# Tiefenentladeschutz-addon.net
KiCad netlist of a schematic drawn in EAGLE
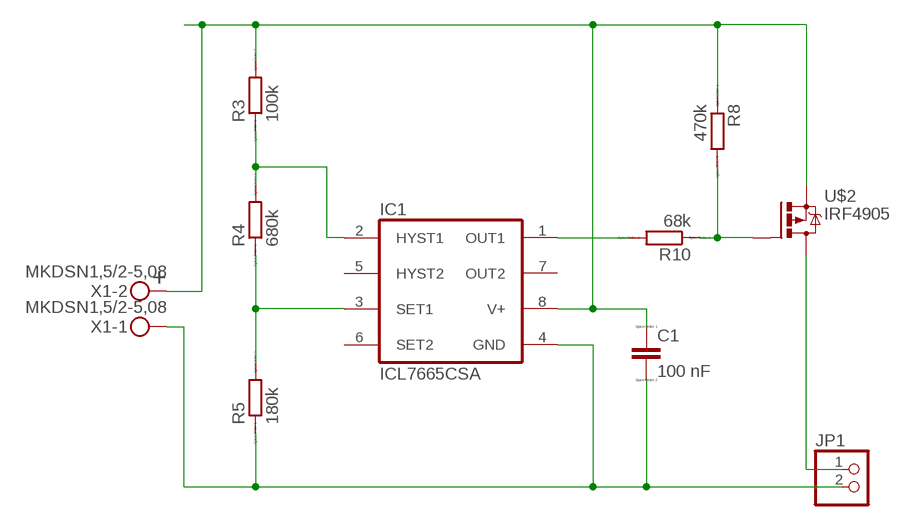
[diagram p0: schematic, sheet 1]

(export (version "E")
  (design (tool "Eeschema 10.0.6"))
  (components
    (comp (ref "C1")
      (value "100 nF")
      (footprint "eagle-import:C0603")
      (libsource (lib "eagle-import") (part "CC0603"))
    )
    (comp (ref "IC1")
      (value "ICL7665CSA")
      (footprint "eagle-import:SO08")
      (fields (field (name "MPN") "ICL7665CSA+"))
      (libsource (lib "eagle-import") (part "ICL7665CSA"))
    )
    (comp (ref "JP1")
      (value "PINHD-1X2")
      (footprint "eagle-import:1X02")
      (libsource (lib "eagle-import") (part "PINHD-1X2"))
    )
    (comp (ref "R3")
      (value "100k")
      (footprint "eagle-import:R1206")
      (libsource (lib "eagle-import") (part "RR1206"))
    )
    (comp (ref "R4")
      (value "680k")
      (footprint "eagle-import:R1206")
      (libsource (lib "eagle-import") (part "RR1206"))
    )
    (comp (ref "R5")
      (value "180k")
      (footprint "eagle-import:R1206")
      (libsource (lib "eagle-import") (part "RR1206"))
    )
    (comp (ref "R8")
      (value "470k")
      (footprint "eagle-import:R1206")
      (libsource (lib "eagle-import") (part "RR1206"))
    )
    (comp (ref "R10")
      (value "68k")
      (footprint "eagle-import:R1206")
      (libsource (lib "eagle-import") (part "RR1206"))
    )
    (comp (ref "U$2")
      (value "IRF4905")
      (footprint "eagle-import:TO220BH")
      (libsource (lib "eagle-import") (part "IRF4905"))
    )
    (comp (ref "X1")
      (value "MKDSN1,5/2-5,08")
      (footprint "eagle-import:MKDSN1,5_2-5,08")
      (libsource (lib "eagle-import") (part "MKDSN1,5/2-5,08"))
    )
  )
  (nets
    (net (code "1") (name "Net-(IC1-GND)") (class "Default")
      (node (ref "C1") (pin "2") (pinfunction "2_2") (pintype "passive"))
      (node (ref "IC1") (pin "4") (pinfunction "GND_4") (pintype "power_in"))
      (node (ref "JP1") (pin "2") (pinfunction "2_2") (pintype "passive"))
      (node (ref "R5") (pin "1") (pinfunction "1_1") (pintype "passive"))
      (node (ref "X1") (pin "1") (pinfunction "KL_1") (pintype "passive"))
    )
    (net (code "2") (name "Net-(IC1-HYST1)") (class "Default")
      (node (ref "IC1") (pin "2") (pinfunction "HYST1_2") (pintype "input"))
      (node (ref "R3") (pin "1") (pinfunction "1_1") (pintype "passive"))
      (node (ref "R4") (pin "2") (pinfunction "2_2") (pintype "passive"))
    )
    (net (code "3") (name "Net-(IC1-OUT1)") (class "Default")
      (node (ref "IC1") (pin "1") (pinfunction "OUT1_1") (pintype "output"))
      (node (ref "R10") (pin "2") (pinfunction "2_2") (pintype "passive"))
    )
    (net (code "4") (name "Net-(IC1-SET1)") (class "Default")
      (node (ref "IC1") (pin "3") (pinfunction "SET1_3") (pintype "input"))
      (node (ref "R4") (pin "1") (pinfunction "1_1") (pintype "passive"))
      (node (ref "R5") (pin "2") (pinfunction "2_2") (pintype "passive"))
    )
    (net (code "5") (name "Net-(IC1-V+)") (class "Default")
      (node (ref "C1") (pin "1") (pinfunction "1_1") (pintype "passive"))
      (node (ref "IC1") (pin "8") (pinfunction "V+_8") (pintype "power_in"))
      (node (ref "R3") (pin "2") (pinfunction "2_2") (pintype "passive"))
      (node (ref "R8") (pin "1") (pinfunction "1_1") (pintype "passive"))
      (node (ref "U$2") (pin "S") (pinfunction "S_S") (pintype "passive"))
      (node (ref "X1") (pin "2") (pinfunction "KL_2") (pintype "passive"))
    )
    (net (code "6") (name "Net-(JP1-Pad1)") (class "Default")
      (node (ref "JP1") (pin "1") (pinfunction "1_1") (pintype "passive"))
      (node (ref "U$2") (pin "D") (pinfunction "D_D") (pintype "passive"))
    )
    (net (code "7") (name "Net-(R10-Pad1)") (class "Default")
      (node (ref "R10") (pin "1") (pinfunction "1_1") (pintype "passive"))
      (node (ref "R8") (pin "2") (pinfunction "2_2") (pintype "passive"))
      (node (ref "U$2") (pin "G") (pinfunction "G_G") (pintype "passive"))
    )
    (net (code "8") (name "unconnected-(IC1-HYST2-Pad5)") (class "Default")
      (node (ref "IC1") (pin "5") (pinfunction "HYST2_5") (pintype "input"))
    )
    (net (code "9") (name "unconnected-(IC1-OUT2-Pad7)") (class "Default")
      (node (ref "IC1") (pin "7") (pinfunction "OUT2_7") (pintype "output"))
    )
    (net (code "10") (name "unconnected-(IC1-SET2-Pad6)") (class "Default")
      (node (ref "IC1") (pin "6") (pinfunction "SET2_6") (pintype "input"))
    )
  )
)
